# 14-100M_Ethernet.net
KiCad netlist of a schematic drawn in Altium Designer
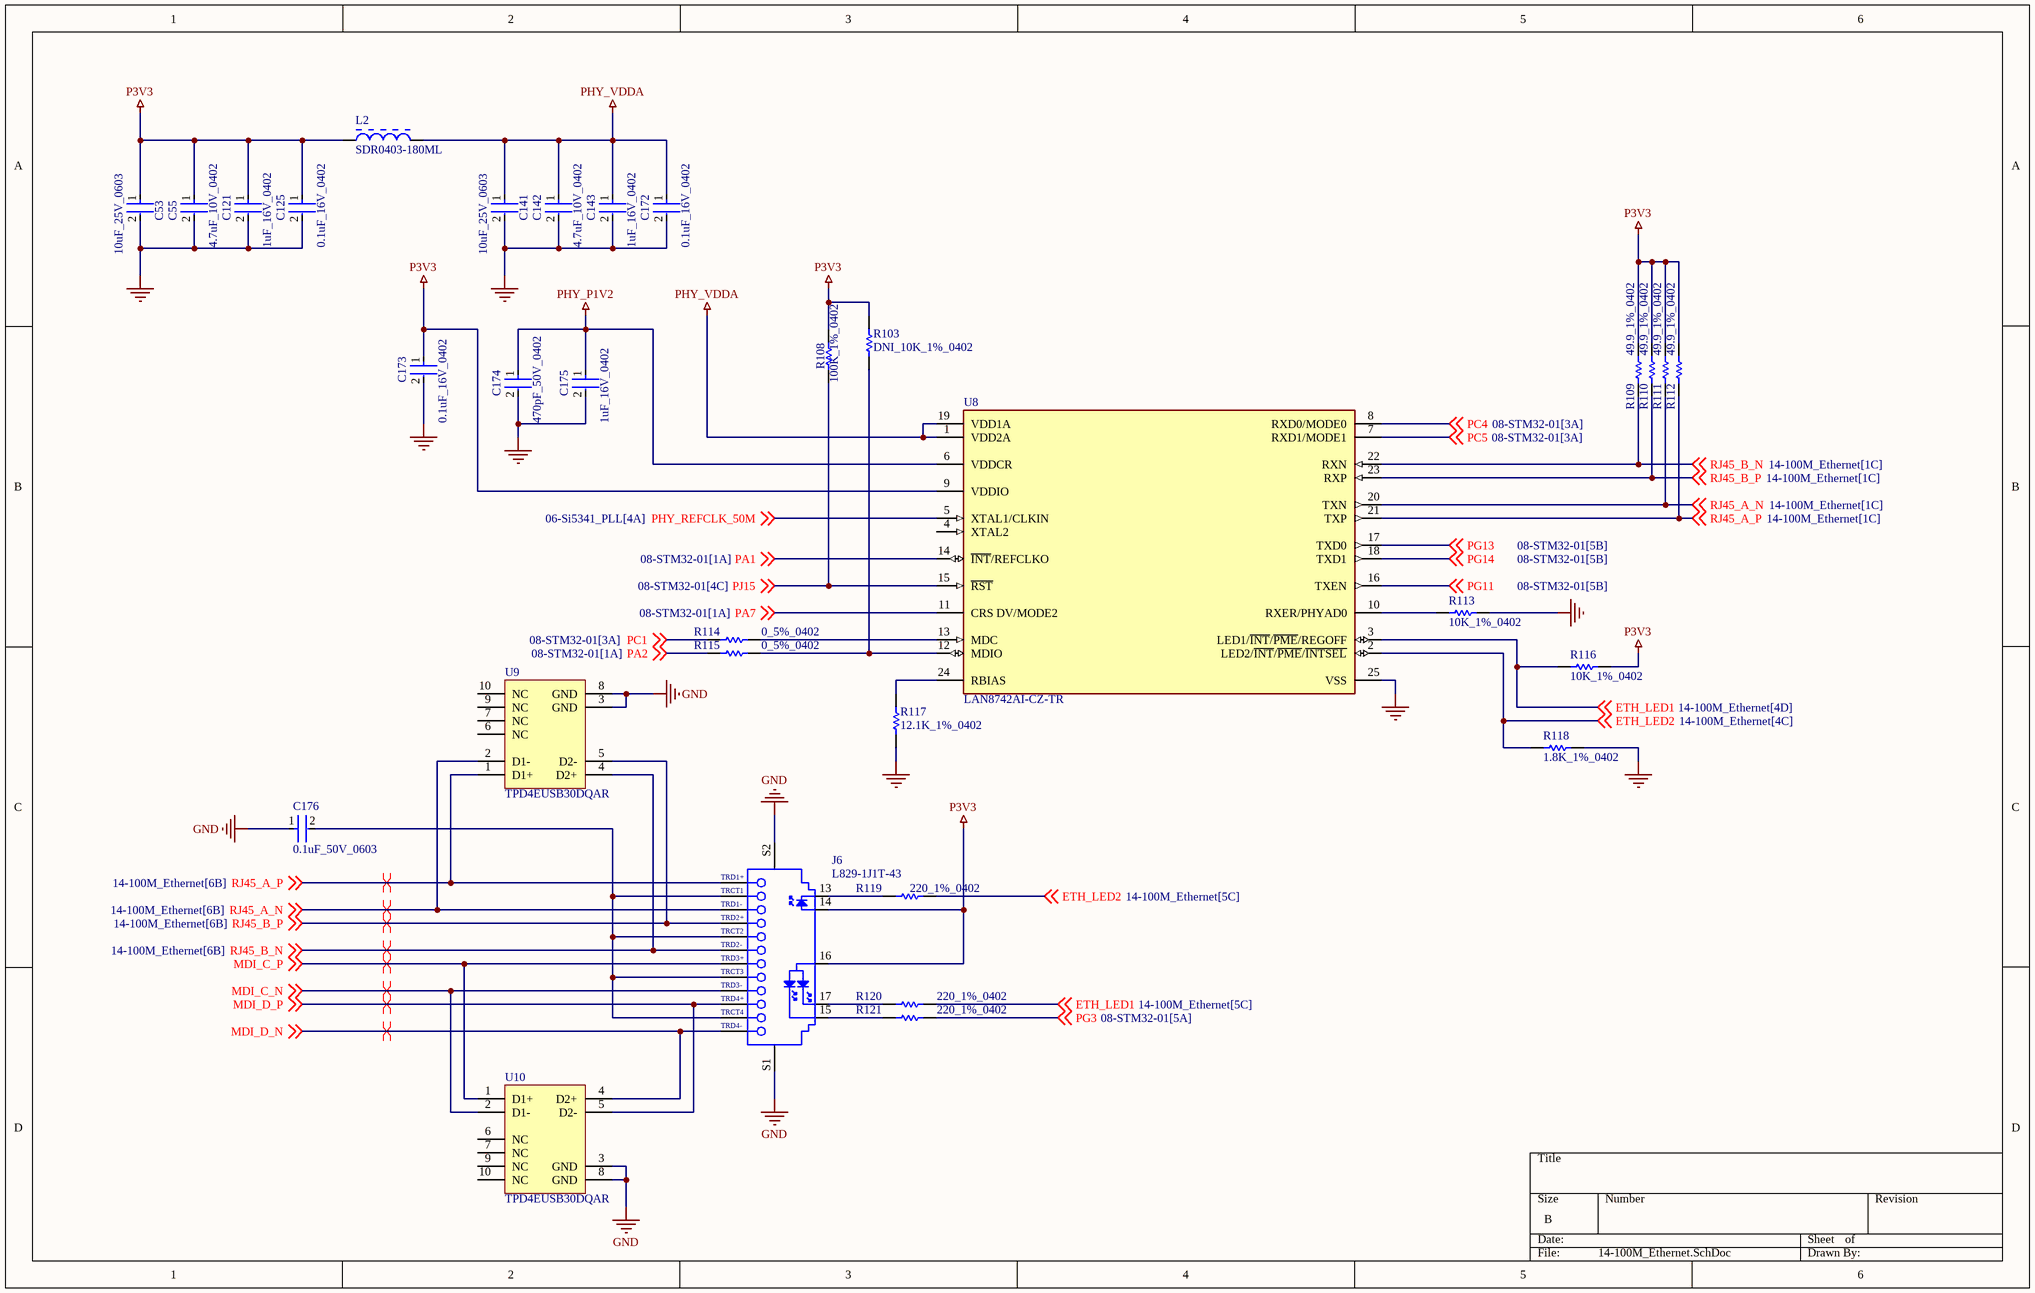
[diagram p0: 14-100M_Ethernet.SchDoc]

(export (version "E")
  (design (tool "Eeschema 10.0.6"))
  (components
    (comp (ref "C53")
      (value "10uF_25V_0603")
      (footprint "FP-CL10-IPC_C")
      (description "Cap Ceramic 10uF 25V X5R ±20% Pad SMD 0603 +85°C T/R")
      (fields (field (name "TOLERANCE") "20%"))
      (libsource (lib "Altium Content Vault") (part "b4654b650e69147ec39a6b967a45e02"))
    )
    (comp (ref "C55")
      (value "4.7uF_10V_0402")
      (footprint "FP-C1005-050-0_15-MFG")
      (description "CAP CER 4.7UF 10V X5R 0402")
      (fields (field (name "TOLERANCE") "10%"))
      (libsource (lib "Altium Content Vault") (part "b4654b650e69147ec39a6b967a45e02"))
    )
    (comp (ref "C121")
      (value "1uF_16V_0402")
      (footprint "FP-0402-L_1_0_0_05-W_0_5-IPC_A")
      (description "None")
      (fields (field (name "TOLERANCE") "10%"))
      (libsource (lib "Altium Content Vault") (part "b4654b650e69147ec39a6b967a45e02"))
    )
    (comp (ref "C125")
      (value "0.1uF_16V_0402")
      (footprint "FP-C0402-BB-MFG")
      (description "CAP CER 0.1UF 16V 5% X7R 0402")
      (fields
        (field (name "MANUFACTURER") "Kemet")
        (field (name "MANUFACTURER PART NUMBER") "C0402C104J4RACTU")
      )
      (libsource (lib "Altium Content Vault") (part "b4654b650e69147ec39a6b967a45e02"))
    )
    (comp (ref "C141")
      (value "10uF_25V_0603")
      (footprint "FP-CL10-IPC_C")
      (description "Cap Ceramic 10uF 25V X5R ±20% Pad SMD 0603 +85°C T/R")
      (fields (field (name "TOLERANCE") "20%"))
      (libsource (lib "Altium Content Vault") (part "b4654b650e69147ec39a6b967a45e02"))
    )
    (comp (ref "C142")
      (value "4.7uF_10V_0402")
      (footprint "FP-C1005-050-0_15-MFG")
      (description "CAP CER 4.7UF 10V X5R 0402")
      (fields (field (name "TOLERANCE") "10%"))
      (libsource (lib "Altium Content Vault") (part "b4654b650e69147ec39a6b967a45e02"))
    )
    (comp (ref "C143")
      (value "1uF_16V_0402")
      (footprint "FP-0402-L_1_0_0_05-W_0_5-IPC_A")
      (description "None")
      (fields (field (name "TOLERANCE") "10%"))
      (libsource (lib "Altium Content Vault") (part "b4654b650e69147ec39a6b967a45e02"))
    )
    (comp (ref "C172")
      (value "0.1uF_16V_0402")
      (footprint "FP-C0402-BB-MFG")
      (description "CAP CER 0.1UF 16V 5% X7R 0402")
      (fields
        (field (name "MANUFACTURER") "Kemet")
        (field (name "MANUFACTURER PART NUMBER") "C0402C104J4RACTU")
      )
      (libsource (lib "Altium Content Vault") (part "b4654b650e69147ec39a6b967a45e02"))
    )
    (comp (ref "C173")
      (value "0.1uF_16V_0402")
      (footprint "FP-C0402-BB-MFG")
      (description "CAP CER 0.1UF 16V 5% X7R 0402")
      (fields
        (field (name "MANUFACTURER") "Kemet")
        (field (name "MANUFACTURER PART NUMBER") "C0402C104J4RACTU")
      )
      (libsource (lib "Altium Content Vault") (part "b4654b650e69147ec39a6b967a45e02"))
    )
    (comp (ref "C174")
      (value "470pF_50V_0402")
      (footprint "FP-GRM155-0_05-IPC_A")
      (description "Chip Multilayer Ceramic Capacitors for General Purpose, 0402, 470pF, C0G, 30ppm/°C, 5%, 50V")
      (fields (field (name "VOLTAGE") "50V") (field (name "TOLERANCE") "5%"))
      (libsource (lib "Altium Content Vault") (part "02cd4be3c70576c341d710602a673aa"))
    )
    (comp (ref "C175")
      (value "1uF_16V_0402")
      (footprint "FP-0402-L_1_0_0_05-W_0_5-IPC_A")
      (description "None")
      (fields (field (name "TOLERANCE") "10%"))
      (libsource (lib "Altium Content Vault") (part "b4654b650e69147ec39a6b967a45e02"))
    )
    (comp (ref "C176")
      (value "0.1uF_50V_0603")
      (footprint "FP-C0603-CJ-MFG")
      (description "CAP CER 0.1UF 50V X7R 0603")
      (fields (field (name "MANUFACTURER PART NUMBER") "C0603X104K5RACTU") (field (name "VOLTAGE") "50V"))
      (libsource (lib "Altium Content Vault") (part "11868f565c42a9108669ba33697ecf6"))
    )
    (comp (ref "J6")
      (value "L829-1J1T-43")
      (footprint "BELS-L829-1J1T-43_V")
      (description "Gigabit MagJack(R) Ultra Low Profile, 10/100/1000 Base-T, 19-Pin THD, RoHS, Tray")
      (libsource (lib "Altium Content Vault") (part "RJ45-17-2SHLD"))
    )
    (comp (ref "L2")
      (value "SDR0403-180ML")
      (footprint "BOUR-SDR0403-2_V")
      (fields (field (name "MANUFACTURER") "Bourns"))
      (libsource (lib "Altium Content Vault") (part "BOUR-IND-2A"))
    )
    (comp (ref "R103")
      (value "DNI_10K_1%_0402")
      (footprint "RESC1005X40X25NL10T10")
      (fields (field (name "MANUFACTURER") "Bourns") (field (name "PART NUMBER") "CR0402-FX-1002GLF"))
      (libsource (lib "Altium Content Vault") (part "RES"))
    )
    (comp (ref "R108")
      (value "100K_1%_0402")
      (footprint "RESC1005X40X25ML05T10")
      (fields (field (name "MANUFACTURER") "Yageo") (field (name "PART NUMBER") "RC0402FR-13100KL"))
      (libsource (lib "Altium Content Vault") (part "RES"))
    )
    (comp (ref "R109")
      (value "49.9_1%_0402")
      (footprint "RESC1005X40X25NL10T10")
      (fields (field (name "PART NUMBER") "RK73H1ETTP49R9F") (field (name "MANUFACTURER") "KOA Speer"))
      (libsource (lib "Altium Content Vault") (part "RES"))
    )
    (comp (ref "R110")
      (value "49.9_1%_0402")
      (footprint "RESC1005X40X25NL10T10")
      (fields (field (name "PART NUMBER") "RK73H1ETTP49R9F") (field (name "MANUFACTURER") "KOA Speer"))
      (libsource (lib "Altium Content Vault") (part "RES"))
    )
    (comp (ref "R111")
      (value "49.9_1%_0402")
      (footprint "RESC1005X40X25NL10T10")
      (fields (field (name "PART NUMBER") "RK73H1ETTP49R9F") (field (name "MANUFACTURER") "KOA Speer"))
      (libsource (lib "Altium Content Vault") (part "RES"))
    )
    (comp (ref "R112")
      (value "49.9_1%_0402")
      (footprint "RESC1005X40X25NL10T10")
      (fields (field (name "PART NUMBER") "RK73H1ETTP49R9F") (field (name "MANUFACTURER") "KOA Speer"))
      (libsource (lib "Altium Content Vault") (part "RES"))
    )
    (comp (ref "R113")
      (value "10K_1%_0402")
      (footprint "RESC1005X40X25NL10T10")
      (fields (field (name "MANUFACTURER") "Bourns") (field (name "PART NUMBER") "CR0402-FX-1002GLF"))
      (libsource (lib "Altium Content Vault") (part "RES"))
    )
    (comp (ref "R114")
      (value "0_5%_0402")
      (footprint "RESC1005X40X25NL05T10")
      (fields (field (name "MANUFACTURER") "Panasonic") (field (name "PART NUMBER") "ERJ-U020R00X"))
      (libsource (lib "Altium Content Vault") (part "RES"))
    )
    (comp (ref "R115")
      (value "0_5%_0402")
      (footprint "RESC1005X40X25NL05T10")
      (fields (field (name "MANUFACTURER") "Panasonic") (field (name "PART NUMBER") "ERJ-U020R00X"))
      (libsource (lib "Altium Content Vault") (part "RES"))
    )
    (comp (ref "R116")
      (value "10K_1%_0402")
      (footprint "RESC1005X40X25NL10T10")
      (fields (field (name "MANUFACTURER") "Bourns") (field (name "PART NUMBER") "CR0402-FX-1002GLF"))
      (libsource (lib "Altium Content Vault") (part "RES"))
    )
    (comp (ref "R117")
      (value "12.1K_1%_0402")
      (footprint "RESC1005X40X25ML05T10")
      (fields (field (name "PART NUMBER") "RC0402FR-0712K1L") (field (name "MANUFACTURER") "Yageo / Phycomp"))
      (libsource (lib "Altium Content Vault") (part "RES"))
    )
    (comp (ref "R118")
      (value "1.8K_1%_0402")
      (footprint "RESC1005X40X25LL05T05")
      (fields (field (name "MANUFACTURER") "Panasonic") (field (name "PART NUMBER") "ERJ2RKF1801X"))
      (libsource (lib "Altium Content Vault") (part "RES"))
    )
    (comp (ref "R119")
      (value "220_1%_0402")
      (footprint "RESC1005X40X25LL10T10")
      (fields (field (name "PART NUMBER") "RK73H1ETTP2200F") (field (name "MANUFACTURER") "KOA Speer"))
      (libsource (lib "Altium Content Vault") (part "RES"))
    )
    (comp (ref "R120")
      (value "220_1%_0402")
      (footprint "RESC1005X40X25LL10T10")
      (fields (field (name "PART NUMBER") "RK73H1ETTP2200F") (field (name "MANUFACTURER") "KOA Speer"))
      (libsource (lib "Altium Content Vault") (part "RES"))
    )
    (comp (ref "R121")
      (value "220_1%_0402")
      (footprint "RESC1005X40X25LL10T10")
      (fields (field (name "PART NUMBER") "RK73H1ETTP2200F") (field (name "MANUFACTURER") "KOA Speer"))
      (libsource (lib "Altium Content Vault") (part "RES"))
    )
    (comp (ref "U8")
      (value "LAN8742AI-CZ-TR")
      (footprint "FP-C04-143-MFG")
      (description "IC TRANSCEIVER FULL 1/1 24SQFN")
      (fields
        (field (name "MANUFACTURER") "Microchip")
        (field (name "OCTOPART") "https://octopart.com/lan8742ai-cz-tr-microchip-29030589")
      )
      (libsource (lib "Altium Content Vault") (part "663acb86b5908f69048389f16eb1286"))
    )
    (comp (ref "U9")
      (value "TPD4EUSB30DQAR")
      (footprint "DQA0010A_V")
      (fields (field (name "MANUFACTURER") "Texas Instruments"))
      (libsource (lib "") (part "TI-TPD4EUSB30-SON_DQA-10_1"))
    )
    (comp (ref "U10")
      (value "TPD4EUSB30DQAR")
      (footprint "DQA0010A_V")
      (fields (field (name "MANUFACTURER") "Texas Instruments"))
      (libsource (lib "Altium Content Vault") (part "TI-TPD4EUSB30-SON_DQA-10"))
    )
  )
  (nets
    (net (code "1") (name "ETH_LED1") (class "Default")
      (node (ref "R116") (pin "2") (pinfunction "2_2") (pintype "passive"))
      (node (ref "R120") (pin "2") (pinfunction "2_2") (pintype "passive"))
      (node (ref "U8") (pin "3") (pinfunction "LED1/~{INT}/~{PME}/REGOFF_3") (pintype "bidirectional"))
    )
    (net (code "2") (name "ETH_LED2") (class "Default")
      (node (ref "R118") (pin "1") (pinfunction "1_1") (pintype "passive"))
      (node (ref "R119") (pin "2") (pinfunction "2_2") (pintype "passive"))
      (node (ref "U8") (pin "2") (pinfunction "LED2/~{INT}/~{PME}/~{INTSEL}_2") (pintype "bidirectional"))
    )
    (net (code "3") (name "GND") (class "Default")
      (node (ref "C121") (pin "2") (pinfunction "2_2") (pintype "passive"))
      (node (ref "C125") (pin "2") (pinfunction "2_2") (pintype "passive"))
      (node (ref "C141") (pin "2") (pinfunction "2_2") (pintype "passive"))
      (node (ref "C142") (pin "2") (pinfunction "2_2") (pintype "passive"))
      (node (ref "C143") (pin "2") (pinfunction "2_2") (pintype "passive"))
      (node (ref "C172") (pin "2") (pinfunction "2_2") (pintype "passive"))
      (node (ref "C173") (pin "2") (pinfunction "2_2") (pintype "passive"))
      (node (ref "C174") (pin "2") (pinfunction "2_2") (pintype "passive"))
      (node (ref "C175") (pin "2") (pinfunction "2_2") (pintype "passive"))
      (node (ref "C176") (pin "1") (pinfunction "1_1") (pintype "passive"))
      (node (ref "C53") (pin "2") (pinfunction "2_2") (pintype "passive"))
      (node (ref "C55") (pin "2") (pinfunction "2_2") (pintype "passive"))
      (node (ref "J6") (pin "S1") (pinfunction "S1_S1") (pintype "passive"))
      (node (ref "J6") (pin "S2") (pinfunction "S2_S2") (pintype "passive"))
      (node (ref "R113") (pin "1") (pinfunction "1_1") (pintype "passive"))
      (node (ref "R117") (pin "1") (pinfunction "1_1") (pintype "passive"))
      (node (ref "R118") (pin "2") (pinfunction "2_2") (pintype "passive"))
      (node (ref "U10") (pin "3") (pinfunction "GND_3") (pintype "power_in"))
      (node (ref "U10") (pin "8") (pinfunction "GND_8") (pintype "power_in"))
      (node (ref "U8") (pin "25") (pinfunction "VSS_25") (pintype "power_in"))
      (node (ref "U9") (pin "3") (pinfunction "GND_3") (pintype "power_in"))
      (node (ref "U9") (pin "8") (pinfunction "GND_8") (pintype "power_in"))
    )
    (net (code "4") (name "MDI_C_N") (class "Default")
      (node (ref "J6") (pin "9") (pinfunction "TRD3-_9") (pintype "passive"))
      (node (ref "U10") (pin "2") (pinfunction "D1-_2") (pintype "passive"))
    )
    (net (code "5") (name "MDI_C_P") (class "Default")
      (node (ref "J6") (pin "7") (pinfunction "TRD3+_7") (pintype "passive"))
      (node (ref "U10") (pin "1") (pinfunction "D1+_1") (pintype "passive"))
    )
    (net (code "6") (name "MDI_D_N") (class "Default")
      (node (ref "J6") (pin "12") (pinfunction "TRD4-_12") (pintype "passive"))
      (node (ref "U10") (pin "4") (pinfunction "D2+_4") (pintype "passive"))
    )
    (net (code "7") (name "MDI_D_P") (class "Default")
      (node (ref "J6") (pin "10") (pinfunction "TRD4+_10") (pintype "passive"))
      (node (ref "U10") (pin "5") (pinfunction "D2-_5") (pintype "passive"))
    )
    (net (code "8") (name "Net-(J6-Pad13)") (class "Default")
      (node (ref "J6") (pin "13") (pinfunction "13_13") (pintype "passive"))
      (node (ref "R119") (pin "1") (pinfunction "1_1") (pintype "passive"))
    )
    (net (code "9") (name "Net-(J6-Pad15)") (class "Default")
      (node (ref "J6") (pin "15") (pinfunction "15_15") (pintype "passive"))
      (node (ref "R121") (pin "1") (pinfunction "1_1") (pintype "passive"))
    )
    (net (code "10") (name "Net-(J6-Pad17)") (class "Default")
      (node (ref "J6") (pin "17") (pinfunction "17_17") (pintype "passive"))
      (node (ref "R120") (pin "1") (pinfunction "1_1") (pintype "passive"))
    )
    (net (code "11") (name "Net-(J6-TRCT1)") (class "Default")
      (node (ref "C176") (pin "2") (pinfunction "2_2") (pintype "passive"))
      (node (ref "J6") (pin "11") (pinfunction "TRCT4_11") (pintype "passive"))
      (node (ref "J6") (pin "2") (pinfunction "TRCT1_2") (pintype "passive"))
      (node (ref "J6") (pin "5") (pinfunction "TRCT2_5") (pintype "passive"))
      (node (ref "J6") (pin "8") (pinfunction "TRCT3_8") (pintype "passive"))
    )
    (net (code "12") (name "Net-(U8-MDC)") (class "Default")
      (node (ref "R114") (pin "2") (pinfunction "2_2") (pintype "passive"))
      (node (ref "U8") (pin "13") (pinfunction "MDC_13") (pintype "input"))
    )
    (net (code "13") (name "Net-(U8-MDIO)") (class "Default")
      (node (ref "R103") (pin "2") (pinfunction "2_2") (pintype "passive"))
      (node (ref "R115") (pin "2") (pinfunction "2_2") (pintype "passive"))
      (node (ref "U8") (pin "12") (pinfunction "MDIO_12") (pintype "bidirectional"))
    )
    (net (code "14") (name "Net-(U8-RBIAS)") (class "Default")
      (node (ref "R117") (pin "2") (pinfunction "2_2") (pintype "passive"))
      (node (ref "U8") (pin "24") (pinfunction "RBIAS_24") (pintype "passive"))
    )
    (net (code "15") (name "Net-(U8-RXER{slash}PHYAD0)") (class "Default")
      (node (ref "R113") (pin "2") (pinfunction "2_2") (pintype "passive"))
      (node (ref "U8") (pin "10") (pinfunction "RXER/PHYAD0_10") (pintype "passive"))
    )
    (net (code "16") (name "P3V3") (class "Default")
      (node (ref "C121") (pin "1") (pinfunction "1_1") (pintype "passive"))
      (node (ref "C125") (pin "1") (pinfunction "1_1") (pintype "passive"))
      (node (ref "C173") (pin "1") (pinfunction "1_1") (pintype "passive"))
      (node (ref "C53") (pin "1") (pinfunction "1_1") (pintype "passive"))
      (node (ref "C55") (pin "1") (pinfunction "1_1") (pintype "passive"))
      (node (ref "J6") (pin "14") (pinfunction "14_14") (pintype "passive"))
      (node (ref "J6") (pin "16") (pinfunction "16_16") (pintype "passive"))
      (node (ref "L2") (pin "1") (pinfunction "1_1") (pintype "passive"))
      (node (ref "R103") (pin "1") (pinfunction "1_1") (pintype "passive"))
      (node (ref "R108") (pin "2") (pinfunction "2_2") (pintype "passive"))
      (node (ref "R109") (pin "1") (pinfunction "1_1") (pintype "passive"))
      (node (ref "R110") (pin "1") (pinfunction "1_1") (pintype "passive"))
      (node (ref "R111") (pin "1") (pinfunction "1_1") (pintype "passive"))
      (node (ref "R112") (pin "1") (pinfunction "1_1") (pintype "passive"))
      (node (ref "R116") (pin "1") (pinfunction "1_1") (pintype "passive"))
      (node (ref "U8") (pin "9") (pinfunction "VDDIO_9") (pintype "power_in"))
    )
    (net (code "17") (name "PA1") (class "Default")
      (node (ref "U8") (pin "14") (pinfunction "~{INT}/REFCLKO_14") (pintype "bidirectional"))
    )
    (net (code "18") (name "PA2") (class "Default")
      (node (ref "R115") (pin "1") (pinfunction "1_1") (pintype "passive"))
    )
    (net (code "19") (name "PA7") (class "Default")
      (node (ref "U8") (pin "11") (pinfunction "CRS_DV/MODE2_11") (pintype "passive"))
    )
    (net (code "20") (name "PC1") (class "Default")
      (node (ref "R114") (pin "1") (pinfunction "1_1") (pintype "passive"))
    )
    (net (code "21") (name "PC4") (class "Default")
      (node (ref "U8") (pin "8") (pinfunction "RXD0/MODE0_8") (pintype "passive"))
    )
    (net (code "22") (name "PC5") (class "Default")
      (node (ref "U8") (pin "7") (pinfunction "RXD1/MODE1_7") (pintype "passive"))
    )
    (net (code "23") (name "PG3") (class "Default")
      (node (ref "R121") (pin "2") (pinfunction "2_2") (pintype "passive"))
    )
    (net (code "24") (name "PG11") (class "Default")
      (node (ref "U8") (pin "16") (pinfunction "TXEN_16") (pintype "output"))
    )
    (net (code "25") (name "PG13") (class "Default")
      (node (ref "U8") (pin "17") (pinfunction "TXD0_17") (pintype "output"))
    )
    (net (code "26") (name "PG14") (class "Default")
      (node (ref "U8") (pin "18") (pinfunction "TXD1_18") (pintype "output"))
    )
    (net (code "27") (name "PHY_P1V2") (class "Default")
      (node (ref "C174") (pin "1") (pinfunction "1_1") (pintype "passive"))
      (node (ref "C175") (pin "1") (pinfunction "1_1") (pintype "passive"))
      (node (ref "U8") (pin "6") (pinfunction "VDDCR_6") (pintype "power_in"))
    )
    (net (code "28") (name "PHY_REFCLK_50M") (class "Default")
      (node (ref "U8") (pin "5") (pinfunction "XTAL1/CLKIN_5") (pintype "input"))
    )
    (net (code "29") (name "PHY_VDDA") (class "Default")
      (node (ref "C141") (pin "1") (pinfunction "1_1") (pintype "passive"))
      (node (ref "C142") (pin "1") (pinfunction "1_1") (pintype "passive"))
      (node (ref "C143") (pin "1") (pinfunction "1_1") (pintype "passive"))
      (node (ref "C172") (pin "1") (pinfunction "1_1") (pintype "passive"))
      (node (ref "L2") (pin "2") (pinfunction "2_2") (pintype "passive"))
      (node (ref "U8") (pin "1") (pinfunction "VDD2A_1") (pintype "power_in"))
      (node (ref "U8") (pin "19") (pinfunction "VDD1A_19") (pintype "power_in"))
    )
    (net (code "30") (name "PJ15") (class "Default")
      (node (ref "R108") (pin "1") (pinfunction "1_1") (pintype "passive"))
      (node (ref "U8") (pin "15") (pinfunction "~{RST}_15") (pintype "input"))
    )
    (net (code "31") (name "RJ45_A_N") (class "Default")
      (node (ref "J6") (pin "3") (pinfunction "TRD1-_3") (pintype "passive"))
      (node (ref "R111") (pin "2") (pinfunction "2_2") (pintype "passive"))
      (node (ref "U8") (pin "20") (pinfunction "TXN_20") (pintype "output"))
      (node (ref "U9") (pin "2") (pinfunction "D1-_2") (pintype "passive"))
    )
    (net (code "32") (name "RJ45_A_P") (class "Default")
      (node (ref "J6") (pin "1") (pinfunction "TRD1+_1") (pintype "passive"))
      (node (ref "R112") (pin "2") (pinfunction "2_2") (pintype "passive"))
      (node (ref "U8") (pin "21") (pinfunction "TXP_21") (pintype "output"))
      (node (ref "U9") (pin "1") (pinfunction "D1+_1") (pintype "passive"))
    )
    (net (code "33") (name "RJ45_B_N") (class "Default")
      (node (ref "J6") (pin "6") (pinfunction "TRD2-_6") (pintype "passive"))
      (node (ref "R109") (pin "2") (pinfunction "2_2") (pintype "passive"))
      (node (ref "U8") (pin "22") (pinfunction "RXN_22") (pintype "input"))
      (node (ref "U9") (pin "4") (pinfunction "D2+_4") (pintype "passive"))
    )
    (net (code "34") (name "RJ45_B_P") (class "Default")
      (node (ref "J6") (pin "4") (pinfunction "TRD2+_4") (pintype "passive"))
      (node (ref "R110") (pin "2") (pinfunction "2_2") (pintype "passive"))
      (node (ref "U8") (pin "23") (pinfunction "RXP_23") (pintype "input"))
      (node (ref "U9") (pin "5") (pinfunction "D2-_5") (pintype "passive"))
    )
    (net (code "35") (name "unconnected-(U8-XTAL2-Pad4)") (class "Default")
      (node (ref "U8") (pin "4") (pinfunction "XTAL2_4") (pintype "input"))
    )
    (net (code "36") (name "unconnected-(U9-NC-Pad6)") (class "Default")
      (node (ref "U9") (pin "6") (pinfunction "NC_6") (pintype "passive"))
    )
    (net (code "37") (name "unconnected-(U9-NC-Pad7)") (class "Default")
      (node (ref "U9") (pin "7") (pinfunction "NC_7") (pintype "passive"))
    )
    (net (code "38") (name "unconnected-(U9-NC-Pad9)") (class "Default")
      (node (ref "U9") (pin "9") (pinfunction "NC_9") (pintype "passive"))
    )
    (net (code "39") (name "unconnected-(U9-NC-Pad10)") (class "Default")
      (node (ref "U9") (pin "10") (pinfunction "NC_10") (pintype "passive"))
    )
    (net (code "40") (name "unconnected-(U10-NC-Pad6)") (class "Default")
      (node (ref "U10") (pin "6") (pinfunction "NC_6") (pintype "passive"))
    )
    (net (code "41") (name "unconnected-(U10-NC-Pad7)") (class "Default")
      (node (ref "U10") (pin "7") (pinfunction "NC_7") (pintype "passive"))
    )
    (net (code "42") (name "unconnected-(U10-NC-Pad9)") (class "Default")
      (node (ref "U10") (pin "9") (pinfunction "NC_9") (pintype "passive"))
    )
    (net (code "43") (name "unconnected-(U10-NC-Pad10)") (class "Default")
      (node (ref "U10") (pin "10") (pinfunction "NC_10") (pintype "passive"))
    )
  )
)
